# Calibrador.net
KiCad netlist of a schematic drawn in EAGLE
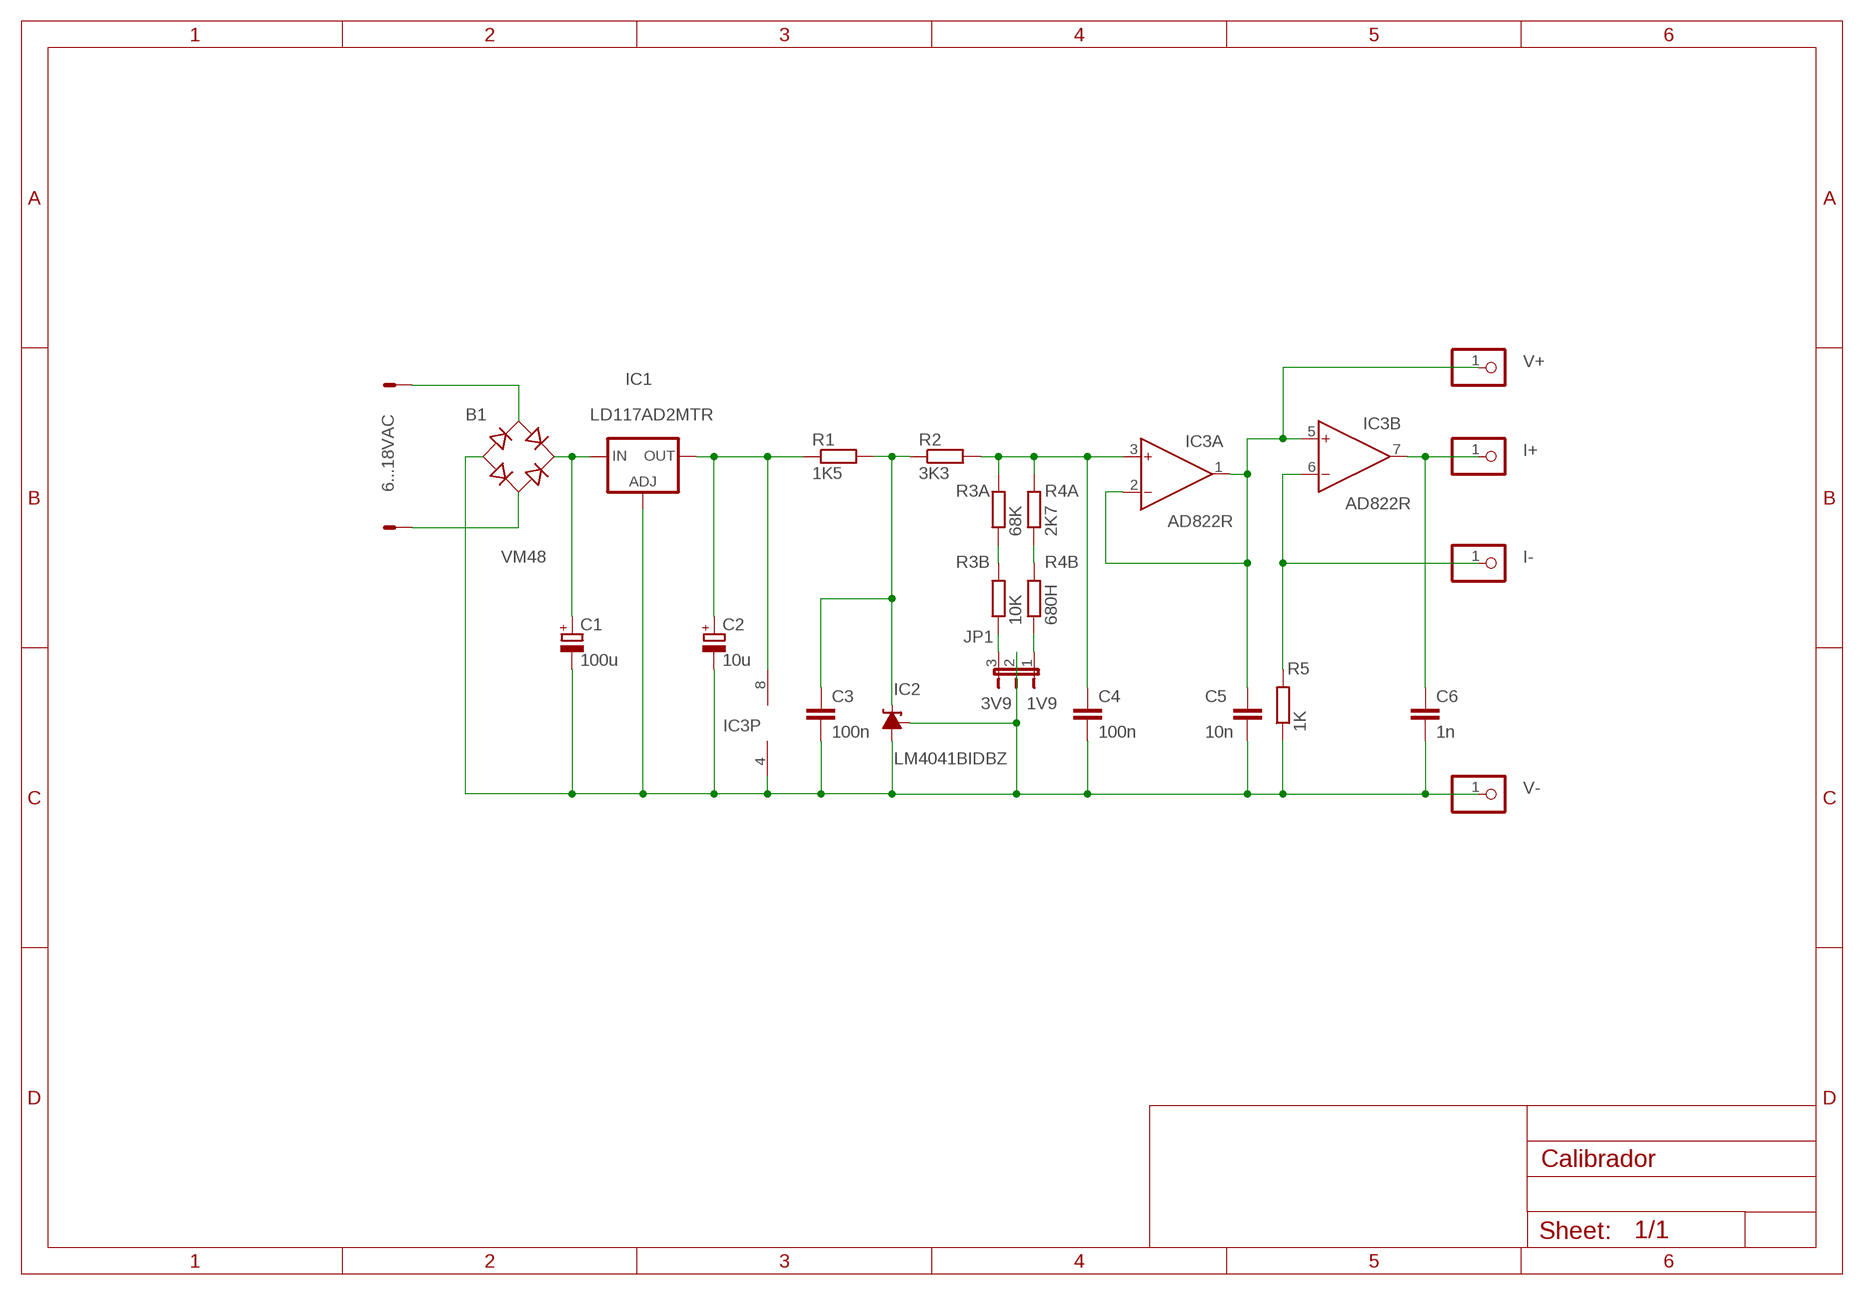
[diagram p0: schematic, sheet 1]

(export (version "E")
  (design (tool "Eeschema 10.0.6"))
  (components
    (comp (ref "B1")
      (value "VM48")
      (footprint "eagle-import:B-DIL")
      (libsource (lib "eagle-import") (part "B-DIL"))
    )
    (comp (ref "C1")
      (value "100u")
      (footprint "eagle-import:153CLV-0807")
      (libsource (lib "eagle-import") (part "CPOL-EU153CLV-0807"))
    )
    (comp (ref "C2")
      (value "10u")
      (footprint "eagle-import:153CLV-0505")
      (libsource (lib "eagle-import") (part "CPOL-EU153CLV-0505"))
    )
    (comp (ref "C3")
      (value "100n")
      (footprint "eagle-import:C0805")
      (libsource (lib "eagle-import") (part "C-EUC0805"))
    )
    (comp (ref "C4")
      (value "100n")
      (footprint "eagle-import:C0805")
      (libsource (lib "eagle-import") (part "C-EUC0805"))
    )
    (comp (ref "C5")
      (value "10n")
      (footprint "eagle-import:C0805")
      (libsource (lib "eagle-import") (part "C-EUC0805"))
    )
    (comp (ref "C6")
      (value "1n")
      (footprint "eagle-import:C0805")
      (libsource (lib "eagle-import") (part "C-EUC0805"))
    )
    (comp (ref "IC1")
      (value "LD117AD2MTR")
      (footprint "eagle-import:D2PACK")
      (libsource (lib "eagle-import") (part "LD117A?D2MTR"))
    )
    (comp (ref "IC2")
      (value "LM4041BIDBZ")
      (footprint "eagle-import:DBZ_R-PDSO-G3")
      (libsource (lib "eagle-import") (part "LM4041IDBZB"))
    )
    (comp (ref "IC3")
      (value "AD822R")
      (footprint "eagle-import:SO8")
      (fields (field (name "MF") "ANALOG DEVICES") (field (name "MPN") "AD822BRZ"))
      (libsource (lib "eagle-import") (part "AD822R"))
    )
    (comp (ref "J1")
      (value "22-27-2021-02")
      (footprint "eagle-import:6410-02")
      (libsource (lib "eagle-import") (part "22-?-0227-2021"))
    )
    (comp (ref "JP1")
      (value "3V9 1V9")
      (footprint "eagle-import:JP2")
      (libsource (lib "eagle-import") (part "JP2E"))
    )
    (comp (ref "JP2")
      (value "V+")
      (footprint "eagle-import:1X01")
      (libsource (lib "eagle-import") (part "PINHD-1X1"))
    )
    (comp (ref "JP3")
      (value "I+")
      (footprint "eagle-import:1X01")
      (libsource (lib "eagle-import") (part "PINHD-1X1"))
    )
    (comp (ref "JP4")
      (value "I-")
      (footprint "eagle-import:1X01")
      (libsource (lib "eagle-import") (part "PINHD-1X1"))
    )
    (comp (ref "JP5")
      (value "V-")
      (footprint "eagle-import:1X01")
      (libsource (lib "eagle-import") (part "PINHD-1X1"))
    )
    (comp (ref "R1")
      (value "1K5")
      (footprint "eagle-import:0207_10")
      (libsource (lib "eagle-import") (part "R-EU_0207/10"))
    )
    (comp (ref "R2")
      (value "3K3")
      (footprint "eagle-import:0207_10")
      (libsource (lib "eagle-import") (part "R-EU_0207/10"))
    )
    (comp (ref "R3A")
      (value "68K")
      (footprint "eagle-import:0207_10")
      (libsource (lib "eagle-import") (part "R-EU_0207/10"))
    )
    (comp (ref "R3B")
      (value "10K")
      (footprint "eagle-import:0207_10")
      (libsource (lib "eagle-import") (part "R-EU_0207/10"))
    )
    (comp (ref "R4A")
      (value "2K7")
      (footprint "eagle-import:0207_10")
      (libsource (lib "eagle-import") (part "R-EU_0207/10"))
    )
    (comp (ref "R4B")
      (value "680H")
      (footprint "eagle-import:0207_10")
      (libsource (lib "eagle-import") (part "R-EU_0207/10"))
    )
    (comp (ref "R5")
      (value "1K")
      (footprint "eagle-import:0207_10")
      (libsource (lib "eagle-import") (part "R-EU_0207/10"))
    )
  )
  (nets
    (net (code "1") (name "Net-(IC1-ADJ)") (class "Default")
      (node (ref "B1") (pin "-") (pinfunction "-_-") (pintype "passive"))
      (node (ref "C1") (pin "-") (pinfunction "-_-") (pintype "passive"))
      (node (ref "C2") (pin "-") (pinfunction "-_-") (pintype "passive"))
      (node (ref "C3") (pin "2") (pinfunction "2_2") (pintype "passive"))
      (node (ref "C4") (pin "2") (pinfunction "2_2") (pintype "passive"))
      (node (ref "C5") (pin "2") (pinfunction "2_2") (pintype "passive"))
      (node (ref "C6") (pin "2") (pinfunction "2_2") (pintype "passive"))
      (node (ref "IC1") (pin "1") (pinfunction "ADJ_1") (pintype "input"))
      (node (ref "IC2") (pin "1") (pinfunction "FB_1") (pintype "passive"))
      (node (ref "IC2") (pin "3") (pinfunction "A_3") (pintype "passive"))
      (node (ref "IC3") (pin "4") (pinfunction "V-_4") (pintype "power_in"))
      (node (ref "JP1") (pin "2") (pinfunction "2_2") (pintype "passive"))
      (node (ref "JP5") (pin "1") (pinfunction "1_1") (pintype "passive"))
      (node (ref "R5") (pin "1") (pinfunction "1_1") (pintype "passive"))
    )
    (net (code "2") (name "Net-(IC1-IN)") (class "Default")
      (node (ref "B1") (pin "+") (pinfunction "+_+") (pintype "passive"))
      (node (ref "C1") (pin "+") (pinfunction "+_+") (pintype "passive"))
      (node (ref "IC1") (pin "3") (pinfunction "IN_3") (pintype "input"))
    )
    (net (code "3") (name "Net-(IC1-OUT)") (class "Default")
      (node (ref "C2") (pin "+") (pinfunction "+_+") (pintype "passive"))
      (node (ref "IC1") (pin "2") (pinfunction "OUT_2") (pintype "passive"))
      (node (ref "IC3") (pin "8") (pinfunction "V+_8") (pintype "power_in"))
      (node (ref "R1") (pin "1") (pinfunction "1_1") (pintype "passive"))
    )
    (net (code "4") (name "Net-(IC2-C)") (class "Default")
      (node (ref "C3") (pin "1") (pinfunction "1_1") (pintype "passive"))
      (node (ref "IC2") (pin "2") (pinfunction "C_2") (pintype "passive"))
      (node (ref "R1") (pin "2") (pinfunction "2_2") (pintype "passive"))
      (node (ref "R2") (pin "1") (pinfunction "1_1") (pintype "passive"))
    )
    (net (code "5") (name "Net-(IC3A-IN+)") (class "Default")
      (node (ref "C4") (pin "1") (pinfunction "1_1") (pintype "passive"))
      (node (ref "IC3") (pin "3") (pinfunction "IN+_3") (pintype "input"))
      (node (ref "R2") (pin "2") (pinfunction "2_2") (pintype "passive"))
      (node (ref "R3A") (pin "2") (pinfunction "2_2") (pintype "passive"))
      (node (ref "R4A") (pin "2") (pinfunction "2_2") (pintype "passive"))
    )
    (net (code "6") (name "Net-(IC3A-IN-)") (class "Default")
      (node (ref "C5") (pin "1") (pinfunction "1_1") (pintype "passive"))
      (node (ref "IC3") (pin "1") (pinfunction "OUT_1") (pintype "output"))
      (node (ref "IC3") (pin "2") (pinfunction "IN-_2") (pintype "input"))
      (node (ref "IC3") (pin "5") (pinfunction "IN+_5") (pintype "input"))
      (node (ref "JP2") (pin "1") (pinfunction "1_1") (pintype "passive"))
    )
    (net (code "7") (name "Net-(IC3B-IN-)") (class "Default")
      (node (ref "IC3") (pin "6") (pinfunction "IN-_6") (pintype "input"))
      (node (ref "JP4") (pin "1") (pinfunction "1_1") (pintype "passive"))
      (node (ref "R5") (pin "2") (pinfunction "2_2") (pintype "passive"))
    )
    (net (code "8") (name "Net-(IC3B-OUT)") (class "Default")
      (node (ref "C6") (pin "1") (pinfunction "1_1") (pintype "passive"))
      (node (ref "IC3") (pin "7") (pinfunction "OUT_7") (pintype "output"))
      (node (ref "JP3") (pin "1") (pinfunction "1_1") (pintype "passive"))
    )
    (net (code "9") (name "Net-(J1A-S)") (class "Default")
      (node (ref "B1") (pin "AC2") (pinfunction "AC2_AC2") (pintype "passive"))
      (node (ref "J1") (pin "1") (pinfunction "S_1") (pintype "passive"))
    )
    (net (code "10") (name "Net-(J1B-S)") (class "Default")
      (node (ref "B1") (pin "AC1") (pinfunction "AC1_AC1") (pintype "passive"))
      (node (ref "J1") (pin "2") (pinfunction "S_2") (pintype "passive"))
    )
    (net (code "11") (name "Net-(JP1-Pad1)") (class "Default")
      (node (ref "JP1") (pin "1") (pinfunction "1_1") (pintype "passive"))
      (node (ref "R4B") (pin "1") (pinfunction "1_1") (pintype "passive"))
    )
    (net (code "12") (name "Net-(JP1-Pad3)") (class "Default")
      (node (ref "JP1") (pin "3") (pinfunction "3_3") (pintype "passive"))
      (node (ref "R3B") (pin "1") (pinfunction "1_1") (pintype "passive"))
    )
    (net (code "13") (name "Net-(R3A-Pad1)") (class "Default")
      (node (ref "R3A") (pin "1") (pinfunction "1_1") (pintype "passive"))
      (node (ref "R3B") (pin "2") (pinfunction "2_2") (pintype "passive"))
    )
    (net (code "14") (name "Net-(R4A-Pad1)") (class "Default")
      (node (ref "R4A") (pin "1") (pinfunction "1_1") (pintype "passive"))
      (node (ref "R4B") (pin "2") (pinfunction "2_2") (pintype "passive"))
    )
  )
)
